# ProtectionCPLD.net
KiCad netlist of a schematic drawn in Altium Designer
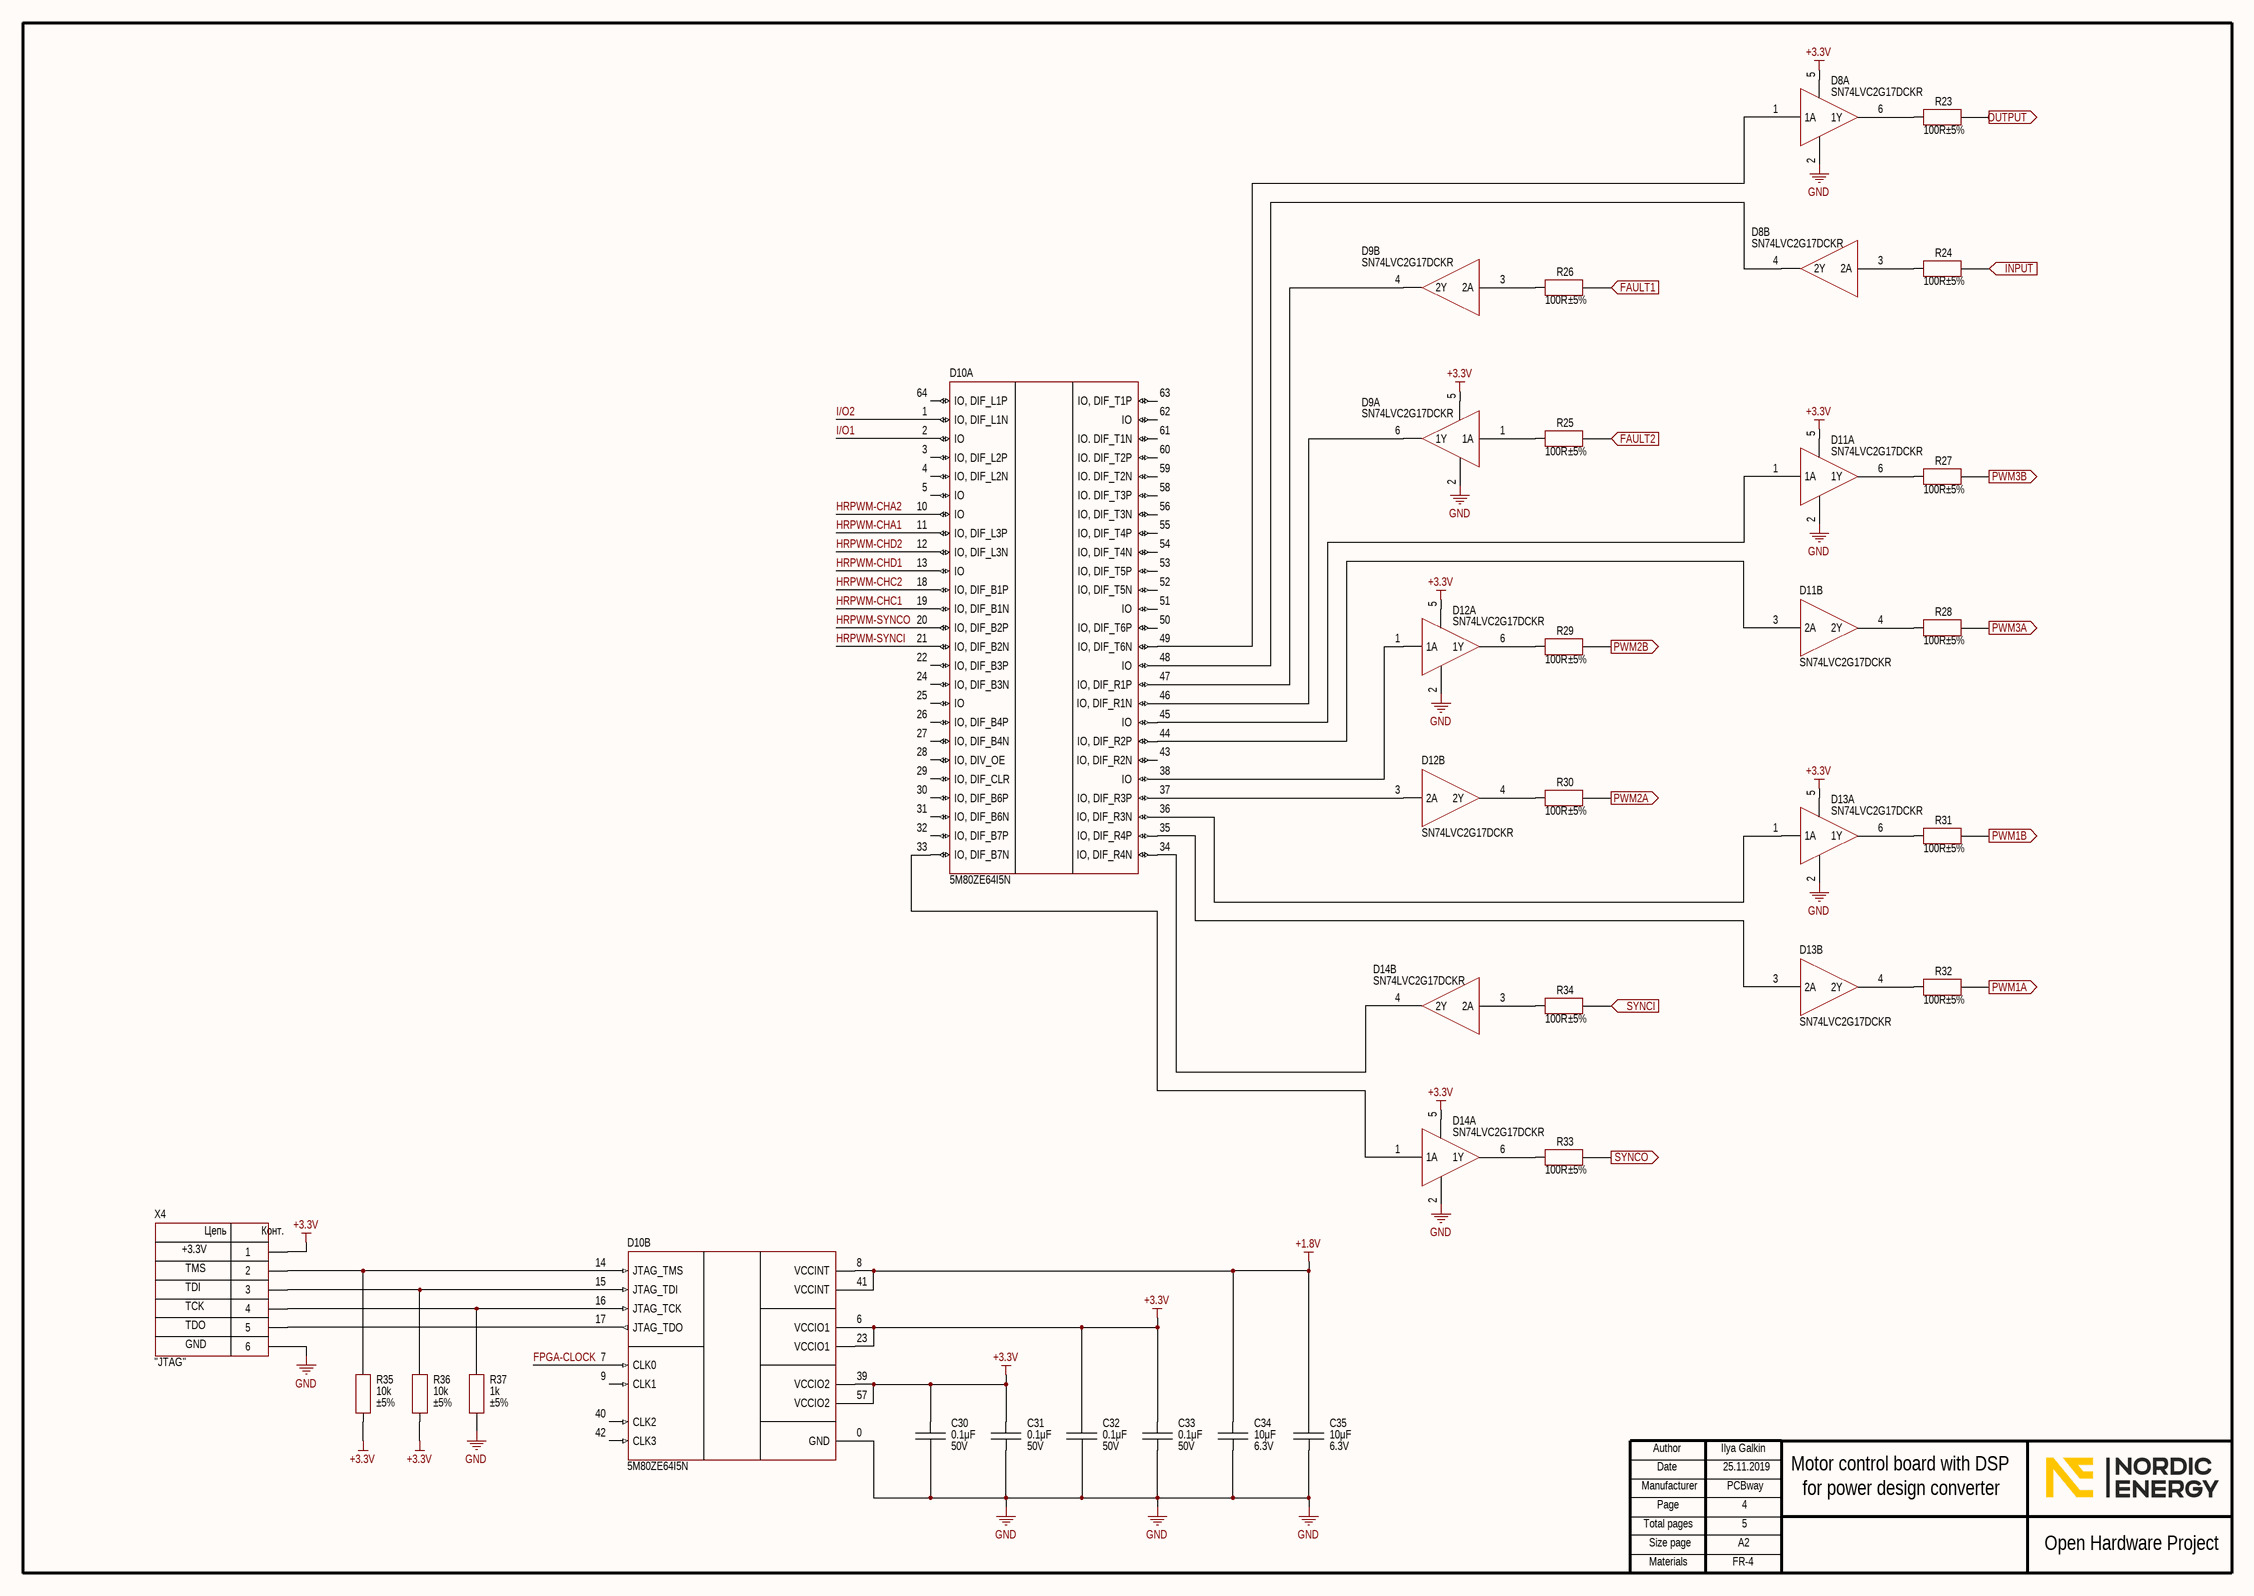
[diagram p0: ProtectionCPLD.SchDoc]

(export (version "E")
  (design (tool "Eeschema 10.0.6"))
  (components
    (comp (ref "C30")
      (value "0.1μF")
      (footprint "CAP: 0603")
      (fields
        (field (name "MANUFACTURER") "Samsung")
        (field (name "PARTNUMBER") "CL10B104KB8NNNC")
        (field (name "VALUEMANUFACTURERPARTNUMBER") "Ceramic capacitor, 0.1μF, X7R, ±10%, 50V, 0603, -55...+125°C")
        (field (name "VOLTAGE") "50V")
      )
      (libsource (lib "Capacitor") (part "Ceramic_0603"))
    )
    (comp (ref "C31")
      (value "0.1μF")
      (footprint "CAP: 0603")
      (fields
        (field (name "MANUFACTURER") "Samsung")
        (field (name "PARTNUMBER") "CL10B104KB8NNNC")
        (field (name "VALUEMANUFACTURERPARTNUMBER") "Ceramic capacitor, 0.1μF, X7R, ±10%, 50V, 0603, -55...+125°C")
        (field (name "VOLTAGE") "50V")
      )
      (libsource (lib "Capacitor") (part "Ceramic_0603"))
    )
    (comp (ref "C32")
      (value "0.1μF")
      (footprint "CAP: 0603")
      (fields
        (field (name "MANUFACTURER") "Samsung")
        (field (name "PARTNUMBER") "CL10B104KB8NNNC")
        (field (name "VALUEMANUFACTURERPARTNUMBER") "Ceramic capacitor, 0.1μF, X7R, ±10%, 50V, 0603, -55...+125°C")
        (field (name "VOLTAGE") "50V")
      )
      (libsource (lib "Capacitor") (part "Ceramic_0603"))
    )
    (comp (ref "C33")
      (value "0.1μF")
      (footprint "CAP: 0603")
      (fields
        (field (name "MANUFACTURER") "Samsung")
        (field (name "PARTNUMBER") "CL10B104KB8NNNC")
        (field (name "VALUEMANUFACTURERPARTNUMBER") "Ceramic capacitor, 0.1μF, X7R, ±10%, 50V, 0603, -55...+125°C")
        (field (name "VOLTAGE") "50V")
      )
      (libsource (lib "Capacitor") (part "Ceramic_0603"))
    )
    (comp (ref "C34")
      (value "10μF")
      (footprint "CAP: 0603")
      (fields
        (field (name "MANUFACTURER") "Samsung")
        (field (name "PARTNUMBER") "CL10B106MQ8NRNC")
        (field (name "VALUEMANUFACTURERPARTNUMBER") "Ceramic capacitor, 10μF, X7R, ±10%, 6.3V, 0603, -55...+125°C")
        (field (name "VOLTAGE") "6.3V")
      )
      (libsource (lib "Capacitor") (part "Ceramic_0603"))
    )
    (comp (ref "C35")
      (value "10μF")
      (footprint "CAP: 0603")
      (fields
        (field (name "MANUFACTURER") "Samsung")
        (field (name "PARTNUMBER") "CL10B106MQ8NRNC")
        (field (name "VALUEMANUFACTURERPARTNUMBER") "Ceramic capacitor, 10μF, X7R, ±10%, 6.3V, 0603, -55...+125°C")
        (field (name "VOLTAGE") "6.3V")
      )
      (libsource (lib "Capacitor") (part "Ceramic_0603"))
    )
    (comp (ref "D8")
      (value "~")
      (footprint "SC70-6")
      (description "Buffer")
      (fields
        (field (name "MANUFACTURER") "Texas Instruments")
        (field (name "VALUEMANUFACTURERPARTNUMBER") "IC logic buffer, 1.65...5.5V, -40...+125°C, SC-70-6")
        (field (name "PARTNUMBER") "SN74LVC2G17DCKR")
      )
      (libsource (lib "IC. Logic") (part "SN74LVC2G17DCKR"))
    )
    (comp (ref "D9")
      (value "~")
      (footprint "SC70-6")
      (description "Buffer")
      (fields
        (field (name "MANUFACTURER") "Texas Instruments")
        (field (name "VALUEMANUFACTURERPARTNUMBER") "IC logic buffer, 1.65...5.5V, -40...+125°C, SC-70-6")
        (field (name "PARTNUMBER") "SN74LVC2G17DCKR")
      )
      (libsource (lib "IC. Logic") (part "SN74LVC2G17DCKR"))
    )
    (comp (ref "D10")
      (value "~")
      (footprint "64-EQFP")
      (description "CPLD Max V")
      (fields
        (field (name "MANUFACTURER") "Intel")
        (field (name "VALUEMANUFACTURERPARTNUMBER") "IC CPLD logic, MAX V, 100MHz, 80LE, 1.71...1.89V, -40...+100°C, 64-EQFP")
        (field (name "PARTNUMBER") "5M80ZE64I5N")
      )
      (libsource (lib "") (part "5M80ZE64I5N_1"))
    )
    (comp (ref "D11")
      (value "~")
      (footprint "SC70-6")
      (description "Buffer")
      (fields
        (field (name "MANUFACTURER") "Texas Instruments")
        (field (name "VALUEMANUFACTURERPARTNUMBER") "IC logic buffer, 1.65...5.5V, -40...+125°C, SC-70-6")
        (field (name "PARTNUMBER") "SN74LVC2G17DCKR")
      )
      (libsource (lib "IC. Logic") (part "SN74LVC2G17DCKR"))
    )
    (comp (ref "D12")
      (value "~")
      (footprint "SC70-6")
      (description "Buffer")
      (fields
        (field (name "MANUFACTURER") "Texas Instruments")
        (field (name "VALUEMANUFACTURERPARTNUMBER") "IC logic buffer, 1.65...5.5V, -40...+125°C, SC-70-6")
        (field (name "PARTNUMBER") "SN74LVC2G17DCKR")
      )
      (libsource (lib "IC. Logic") (part "SN74LVC2G17DCKR"))
    )
    (comp (ref "D13")
      (value "~")
      (footprint "SC70-6")
      (description "Buffer")
      (fields
        (field (name "MANUFACTURER") "Texas Instruments")
        (field (name "VALUEMANUFACTURERPARTNUMBER") "IC logic buffer, 1.65...5.5V, -40...+125°C, SC-70-6")
        (field (name "PARTNUMBER") "SN74LVC2G17DCKR")
      )
      (libsource (lib "IC. Logic") (part "SN74LVC2G17DCKR"))
    )
    (comp (ref "D14")
      (value "~")
      (footprint "SC70-6")
      (description "Buffer")
      (fields
        (field (name "MANUFACTURER") "Texas Instruments")
        (field (name "VALUEMANUFACTURERPARTNUMBER") "IC logic buffer, 1.65...5.5V, -40...+125°C, SC-70-6")
        (field (name "PARTNUMBER") "SN74LVC2G17DCKR")
      )
      (libsource (lib "IC. Logic") (part "SN74LVC2G17DCKR"))
    )
    (comp (ref "R23")
      (value "100R")
      (footprint "RES: 0603")
      (fields
        (field (name "MANUFACTURER") "Yageo")
        (field (name "PARTNUMBER") "RC0603JR-07100RL")
        (field (name "VALUEMANUFACTURERPARTNUMBER") "Resistor film, 100R, ±5%, 0603, 0.1W, -55...+125°C")
        (field (name "TOLERANCE") "±5%")
      )
      (libsource (lib "Resistor") (part "Resistor_0603"))
    )
    (comp (ref "R24")
      (value "100R")
      (footprint "RES: 0603")
      (fields
        (field (name "MANUFACTURER") "Yageo")
        (field (name "PARTNUMBER") "RC0603JR-07100RL")
        (field (name "VALUEMANUFACTURERPARTNUMBER") "Resistor film, 100R, ±5%, 0603, 0.1W, -55...+125°C")
        (field (name "TOLERANCE") "±5%")
      )
      (libsource (lib "Resistor") (part "Resistor_0603"))
    )
    (comp (ref "R25")
      (value "100R")
      (footprint "RES: 0603")
      (fields
        (field (name "MANUFACTURER") "Yageo")
        (field (name "PARTNUMBER") "RC0603JR-07100RL")
        (field (name "VALUEMANUFACTURERPARTNUMBER") "Resistor film, 100R, ±5%, 0603, 0.1W, -55...+125°C")
        (field (name "TOLERANCE") "±5%")
      )
      (libsource (lib "Resistor") (part "Resistor_0603"))
    )
    (comp (ref "R26")
      (value "100R")
      (footprint "RES: 0603")
      (fields
        (field (name "MANUFACTURER") "Yageo")
        (field (name "PARTNUMBER") "RC0603JR-07100RL")
        (field (name "VALUEMANUFACTURERPARTNUMBER") "Resistor film, 100R, ±5%, 0603, 0.1W, -55...+125°C")
        (field (name "TOLERANCE") "±5%")
      )
      (libsource (lib "Resistor") (part "Resistor_0603"))
    )
    (comp (ref "R27")
      (value "100R")
      (footprint "RES: 0603")
      (fields
        (field (name "MANUFACTURER") "Yageo")
        (field (name "PARTNUMBER") "RC0603JR-07100RL")
        (field (name "VALUEMANUFACTURERPARTNUMBER") "Resistor film, 100R, ±5%, 0603, 0.1W, -55...+125°C")
        (field (name "TOLERANCE") "±5%")
      )
      (libsource (lib "Resistor") (part "Resistor_0603"))
    )
    (comp (ref "R28")
      (value "100R")
      (footprint "RES: 0603")
      (fields
        (field (name "MANUFACTURER") "Yageo")
        (field (name "PARTNUMBER") "RC0603JR-07100RL")
        (field (name "VALUEMANUFACTURERPARTNUMBER") "Resistor film, 100R, ±5%, 0603, 0.1W, -55...+125°C")
        (field (name "TOLERANCE") "±5%")
      )
      (libsource (lib "Resistor") (part "Resistor_0603"))
    )
    (comp (ref "R29")
      (value "100R")
      (footprint "RES: 0603")
      (fields
        (field (name "MANUFACTURER") "Yageo")
        (field (name "PARTNUMBER") "RC0603JR-07100RL")
        (field (name "VALUEMANUFACTURERPARTNUMBER") "Resistor film, 100R, ±5%, 0603, 0.1W, -55...+125°C")
        (field (name "TOLERANCE") "±5%")
      )
      (libsource (lib "Resistor") (part "Resistor_0603"))
    )
    (comp (ref "R30")
      (value "100R")
      (footprint "RES: 0603")
      (fields
        (field (name "MANUFACTURER") "Yageo")
        (field (name "PARTNUMBER") "RC0603JR-07100RL")
        (field (name "VALUEMANUFACTURERPARTNUMBER") "Resistor film, 100R, ±5%, 0603, 0.1W, -55...+125°C")
        (field (name "TOLERANCE") "±5%")
      )
      (libsource (lib "Resistor") (part "Resistor_0603"))
    )
    (comp (ref "R31")
      (value "100R")
      (footprint "RES: 0603")
      (fields
        (field (name "MANUFACTURER") "Yageo")
        (field (name "PARTNUMBER") "RC0603JR-07100RL")
        (field (name "VALUEMANUFACTURERPARTNUMBER") "Resistor film, 100R, ±5%, 0603, 0.1W, -55...+125°C")
        (field (name "TOLERANCE") "±5%")
      )
      (libsource (lib "Resistor") (part "Resistor_0603"))
    )
    (comp (ref "R32")
      (value "100R")
      (footprint "RES: 0603")
      (fields
        (field (name "MANUFACTURER") "Yageo")
        (field (name "PARTNUMBER") "RC0603JR-07100RL")
        (field (name "VALUEMANUFACTURERPARTNUMBER") "Resistor film, 100R, ±5%, 0603, 0.1W, -55...+125°C")
        (field (name "TOLERANCE") "±5%")
      )
      (libsource (lib "Resistor") (part "Resistor_0603"))
    )
    (comp (ref "R33")
      (value "100R")
      (footprint "RES: 0603")
      (fields
        (field (name "MANUFACTURER") "Yageo")
        (field (name "PARTNUMBER") "RC0603JR-07100RL")
        (field (name "VALUEMANUFACTURERPARTNUMBER") "Resistor film, 100R, ±5%, 0603, 0.1W, -55...+125°C")
        (field (name "TOLERANCE") "±5%")
      )
      (libsource (lib "Resistor") (part "Resistor_0603"))
    )
    (comp (ref "R34")
      (value "100R")
      (footprint "RES: 0603")
      (fields
        (field (name "MANUFACTURER") "Yageo")
        (field (name "PARTNUMBER") "RC0603JR-07100RL")
        (field (name "VALUEMANUFACTURERPARTNUMBER") "Resistor film, 100R, ±5%, 0603, 0.1W, -55...+125°C")
        (field (name "TOLERANCE") "±5%")
      )
      (libsource (lib "Resistor") (part "Resistor_0603"))
    )
    (comp (ref "R35")
      (value "10k")
      (footprint "RES: 0603")
      (fields
        (field (name "MANUFACTURER") "Yageo")
        (field (name "PARTNUMBER") "RC0603JR-0710KL")
        (field (name "VALUEMANUFACTURERPARTNUMBER") "Resistor film, 10k, ±5%, 0603, 0.1W, -55...+125°C")
        (field (name "TOLERANCE") "±5%")
      )
      (libsource (lib "") (part "Resistor_0603_1"))
    )
    (comp (ref "R36")
      (value "10k")
      (footprint "RES: 0603")
      (fields
        (field (name "MANUFACTURER") "Yageo")
        (field (name "PARTNUMBER") "RC0603JR-0710KL")
        (field (name "VALUEMANUFACTURERPARTNUMBER") "Resistor film, 10k, ±5%, 0603, 0.1W, -55...+125°C")
        (field (name "TOLERANCE") "±5%")
      )
      (libsource (lib "") (part "Resistor_0603_1"))
    )
    (comp (ref "R37")
      (value "1k")
      (footprint "RES: 0603")
      (fields
        (field (name "MANUFACTURER") "Yageo")
        (field (name "PARTNUMBER") "RC0603JR-071KL")
        (field (name "VALUEMANUFACTURERPARTNUMBER") "Resistor film, 1k, ±5%, 0603, 0.1W, -55...+125°C")
        (field (name "TOLERANCE") "±5%")
      )
      (libsource (lib "") (part "Resistor_0603_1"))
    )
    (comp (ref "X4")
      (value "~")
      (footprint "CON: SM06B-GHS")
      (fields
        (field (name "MANUFACTURER") "JST")
        (field (name "VALUEMANUFACTURERPARTNUMBER") "Connector, 6pin, 1.25mm, 50VDC, 1A")
        (field (name "PARTNUMBER") "SM06B-GHS")
        (field (name "COMMENTTEXT") "\"JTAG\"")
      )
      (libsource (lib "Connector") (part "Connector_SM06B"))
    )
  )
  (nets
    (net (code "1") (name "+1.8V") (class "Default")
      (node (ref "C34") (pin "2") (pinfunction "2_2") (pintype "power_in"))
      (node (ref "C35") (pin "2") (pinfunction "2_2") (pintype "power_in"))
      (node (ref "D10") (pin "41") (pinfunction "VCCINT_41") (pintype "power_in"))
      (node (ref "D10") (pin "8") (pinfunction "VCCINT_8") (pintype "power_in"))
    )
    (net (code "2") (name "+3.3V") (class "Default")
      (node (ref "C30") (pin "2") (pinfunction "2_2") (pintype "power_in"))
      (node (ref "C31") (pin "2") (pinfunction "2_2") (pintype "power_in"))
      (node (ref "C32") (pin "2") (pinfunction "2_2") (pintype "power_in"))
      (node (ref "C33") (pin "2") (pinfunction "2_2") (pintype "power_in"))
      (node (ref "D10") (pin "23") (pinfunction "VCCIO1_23") (pintype "power_in"))
      (node (ref "D10") (pin "39") (pinfunction "VCCIO2_39") (pintype "power_in"))
      (node (ref "D10") (pin "57") (pinfunction "VCCIO2_57") (pintype "power_in"))
      (node (ref "D10") (pin "6") (pinfunction "VCCIO1_6") (pintype "power_in"))
      (node (ref "D11") (pin "5") (pintype "passive"))
      (node (ref "D12") (pin "5") (pintype "passive"))
      (node (ref "D13") (pin "5") (pintype "passive"))
      (node (ref "D14") (pin "5") (pintype "passive"))
      (node (ref "D8") (pin "5") (pintype "passive"))
      (node (ref "D9") (pin "5") (pintype "passive"))
      (node (ref "R35") (pin "1") (pinfunction "1_1") (pintype "passive"))
      (node (ref "R36") (pin "1") (pinfunction "1_1") (pintype "passive"))
      (node (ref "X4") (pin "1") (pinfunction "1_1") (pintype "passive"))
    )
    (net (code "3") (name "/FAULT1") (class "Default")
      (node (ref "R26") (pin "2") (pinfunction "2_2") (pintype "passive"))
    )
    (net (code "4") (name "/FAULT2") (class "Default")
      (node (ref "R25") (pin "2") (pinfunction "2_2") (pintype "passive"))
    )
    (net (code "5") (name "/FPGA-CLOCK") (class "Default")
      (node (ref "D10") (pin "7") (pinfunction "CLK0_7") (pintype "input"))
    )
    (net (code "6") (name "/HRPWM-CHA1") (class "Default")
      (node (ref "D10") (pin "11") (pinfunction "IO,_DIF_L3P_11") (pintype "bidirectional"))
    )
    (net (code "7") (name "/HRPWM-CHA2") (class "Default")
      (node (ref "D10") (pin "10") (pinfunction "IO_10") (pintype "bidirectional"))
    )
    (net (code "8") (name "/HRPWM-CHC1") (class "Default")
      (node (ref "D10") (pin "19") (pinfunction "IO,_DIF_B1N_19") (pintype "bidirectional"))
    )
    (net (code "9") (name "/HRPWM-CHC2") (class "Default")
      (node (ref "D10") (pin "18") (pinfunction "IO,_DIF_B1P_18") (pintype "bidirectional"))
    )
    (net (code "10") (name "/HRPWM-CHD1") (class "Default")
      (node (ref "D10") (pin "13") (pinfunction "IO_13") (pintype "bidirectional"))
    )
    (net (code "11") (name "/HRPWM-CHD2") (class "Default")
      (node (ref "D10") (pin "12") (pinfunction "IO,_DIF_L3N_12") (pintype "bidirectional"))
    )
    (net (code "12") (name "/HRPWM-SYNCI") (class "Default")
      (node (ref "D10") (pin "21") (pinfunction "IO,_DIF_B2N_21") (pintype "bidirectional"))
    )
    (net (code "13") (name "/HRPWM-SYNCO") (class "Default")
      (node (ref "D10") (pin "20") (pinfunction "IO,_DIF_B2P_20") (pintype "bidirectional"))
    )
    (net (code "14") (name "/INPUT") (class "Default")
      (node (ref "R24") (pin "2") (pinfunction "2_2") (pintype "passive"))
    )
    (net (code "15") (name "/I{slash}O1") (class "Default")
      (node (ref "D10") (pin "2") (pinfunction "IO_2") (pintype "bidirectional"))
    )
    (net (code "16") (name "/I{slash}O2") (class "Default")
      (node (ref "D10") (pin "1") (pinfunction "IO,_DIF_L1N_1") (pintype "bidirectional"))
    )
    (net (code "17") (name "/OUTPUT") (class "Default")
      (node (ref "R23") (pin "2") (pinfunction "2_2") (pintype "passive"))
    )
    (net (code "18") (name "/PWM1A") (class "Default")
      (node (ref "R32") (pin "2") (pinfunction "2_2") (pintype "passive"))
    )
    (net (code "19") (name "/PWM1B") (class "Default")
      (node (ref "R31") (pin "2") (pinfunction "2_2") (pintype "passive"))
    )
    (net (code "20") (name "/PWM2A") (class "Default")
      (node (ref "R30") (pin "2") (pinfunction "2_2") (pintype "passive"))
    )
    (net (code "21") (name "/PWM2B") (class "Default")
      (node (ref "R29") (pin "2") (pinfunction "2_2") (pintype "passive"))
    )
    (net (code "22") (name "/PWM3A") (class "Default")
      (node (ref "R28") (pin "2") (pinfunction "2_2") (pintype "passive"))
    )
    (net (code "23") (name "/PWM3B") (class "Default")
      (node (ref "R27") (pin "2") (pinfunction "2_2") (pintype "passive"))
    )
    (net (code "24") (name "/SYNCI") (class "Default")
      (node (ref "R34") (pin "2") (pinfunction "2_2") (pintype "passive"))
    )
    (net (code "25") (name "/SYNCO") (class "Default")
      (node (ref "R33") (pin "2") (pinfunction "2_2") (pintype "passive"))
    )
    (net (code "26") (name "GND") (class "Default")
      (node (ref "C30") (pin "1") (pinfunction "1_1") (pintype "power_in"))
      (node (ref "C31") (pin "1") (pinfunction "1_1") (pintype "power_in"))
      (node (ref "C32") (pin "1") (pinfunction "1_1") (pintype "power_in"))
      (node (ref "C33") (pin "1") (pinfunction "1_1") (pintype "power_in"))
      (node (ref "C34") (pin "1") (pinfunction "1_1") (pintype "power_in"))
      (node (ref "C35") (pin "1") (pinfunction "1_1") (pintype "power_in"))
      (node (ref "D10") (pin "0") (pinfunction "GND_0") (pintype "power_in"))
      (node (ref "D11") (pin "2") (pintype "passive"))
      (node (ref "D12") (pin "2") (pintype "passive"))
      (node (ref "D13") (pin "2") (pintype "passive"))
      (node (ref "D14") (pin "2") (pintype "passive"))
      (node (ref "D8") (pin "2") (pintype "passive"))
      (node (ref "D9") (pin "2") (pintype "passive"))
      (node (ref "R37") (pin "1") (pinfunction "1_1") (pintype "passive"))
      (node (ref "X4") (pin "6") (pinfunction "6_6") (pintype "power_in"))
    )
    (net (code "27") (name "Net-(D8A-1Y)") (class "Default")
      (node (ref "D8") (pin "6") (pinfunction "1Y_6") (pintype "passive"))
      (node (ref "R23") (pin "1") (pinfunction "1_1") (pintype "passive"))
    )
    (net (code "28") (name "Net-(D8B-2A)") (class "Default")
      (node (ref "D8") (pin "3") (pinfunction "2A_3") (pintype "passive"))
      (node (ref "R24") (pin "1") (pinfunction "1_1") (pintype "passive"))
    )
    (net (code "29") (name "Net-(D8B-2Y)") (class "Default")
      (node (ref "D10") (pin "48") (pinfunction "IO_48") (pintype "bidirectional"))
      (node (ref "D8") (pin "4") (pinfunction "2Y_4") (pintype "passive"))
    )
    (net (code "30") (name "Net-(D9A-1A)") (class "Default")
      (node (ref "D9") (pin "1") (pinfunction "1A_1") (pintype "passive"))
      (node (ref "R25") (pin "1") (pinfunction "1_1") (pintype "passive"))
    )
    (net (code "31") (name "Net-(D9B-2A)") (class "Default")
      (node (ref "D9") (pin "3") (pinfunction "2A_3") (pintype "passive"))
      (node (ref "R26") (pin "1") (pinfunction "1_1") (pintype "passive"))
    )
    (net (code "32") (name "Net-(D10A-IO,_DIF_B7N)") (class "Default")
      (node (ref "D10") (pin "33") (pinfunction "IO,_DIF_B7N_33") (pintype "bidirectional"))
      (node (ref "D14") (pin "1") (pinfunction "1A_1") (pintype "passive"))
    )
    (net (code "33") (name "Net-(D10A-IO,_DIF_R1N)") (class "Default")
      (node (ref "D10") (pin "46") (pinfunction "IO,_DIF_R1N_46") (pintype "bidirectional"))
      (node (ref "D9") (pin "6") (pinfunction "1Y_6") (pintype "passive"))
    )
    (net (code "34") (name "Net-(D10A-IO,_DIF_R1P)") (class "Default")
      (node (ref "D10") (pin "47") (pinfunction "IO,_DIF_R1P_47") (pintype "bidirectional"))
      (node (ref "D9") (pin "4") (pinfunction "2Y_4") (pintype "passive"))
    )
    (net (code "35") (name "Net-(D10A-IO,_DIF_R2P)") (class "Default")
      (node (ref "D10") (pin "44") (pinfunction "IO,_DIF_R2P_44") (pintype "bidirectional"))
      (node (ref "D11") (pin "3") (pinfunction "2A_3") (pintype "passive"))
    )
    (net (code "36") (name "Net-(D10A-IO,_DIF_R3N)") (class "Default")
      (node (ref "D10") (pin "36") (pinfunction "IO,_DIF_R3N_36") (pintype "bidirectional"))
      (node (ref "D13") (pin "1") (pinfunction "1A_1") (pintype "passive"))
    )
    (net (code "37") (name "Net-(D10A-IO,_DIF_R3P)") (class "Default")
      (node (ref "D10") (pin "37") (pinfunction "IO,_DIF_R3P_37") (pintype "bidirectional"))
      (node (ref "D12") (pin "3") (pinfunction "2A_3") (pintype "passive"))
    )
    (net (code "38") (name "Net-(D10A-IO,_DIF_R4N)") (class "Default")
      (node (ref "D10") (pin "34") (pinfunction "IO,_DIF_R4N_34") (pintype "bidirectional"))
      (node (ref "D14") (pin "4") (pinfunction "2Y_4") (pintype "passive"))
    )
    (net (code "39") (name "Net-(D10A-IO,_DIF_R4P)") (class "Default")
      (node (ref "D10") (pin "35") (pinfunction "IO,_DIF_R4P_35") (pintype "bidirectional"))
      (node (ref "D13") (pin "3") (pinfunction "2A_3") (pintype "passive"))
    )
    (net (code "40") (name "Net-(D10A-IO,_DIF_T6N)") (class "Default")
      (node (ref "D10") (pin "49") (pinfunction "IO,_DIF_T6N_49") (pintype "bidirectional"))
      (node (ref "D8") (pin "1") (pinfunction "1A_1") (pintype "passive"))
    )
    (net (code "41") (name "Net-(D10B-JTAG_TCK)") (class "Default")
      (node (ref "D10") (pin "16") (pinfunction "JTAG_TCK_16") (pintype "input"))
      (node (ref "R37") (pin "2") (pinfunction "2_2") (pintype "passive"))
      (node (ref "X4") (pin "4") (pinfunction "4_4") (pintype "power_in"))
    )
    (net (code "42") (name "Net-(D10B-JTAG_TDI)") (class "Default")
      (node (ref "D10") (pin "15") (pinfunction "JTAG_TDI_15") (pintype "input"))
      (node (ref "R36") (pin "2") (pinfunction "2_2") (pintype "passive"))
      (node (ref "X4") (pin "3") (pinfunction "3_3") (pintype "power_in"))
    )
    (net (code "43") (name "Net-(D10B-JTAG_TDO)") (class "Default")
      (node (ref "D10") (pin "17") (pinfunction "JTAG_TDO_17") (pintype "output"))
      (node (ref "X4") (pin "5") (pinfunction "5_5") (pintype "power_in"))
    )
    (net (code "44") (name "Net-(D10B-JTAG_TMS)") (class "Default")
      (node (ref "D10") (pin "14") (pinfunction "JTAG_TMS_14") (pintype "input"))
      (node (ref "R35") (pin "2") (pinfunction "2_2") (pintype "passive"))
      (node (ref "X4") (pin "2") (pinfunction "2_2") (pintype "passive"))
    )
    (net (code "45") (name "Net-(D11A-1A)") (class "Default")
      (node (ref "D10") (pin "45") (pinfunction "IO_45") (pintype "bidirectional"))
      (node (ref "D11") (pin "1") (pinfunction "1A_1") (pintype "passive"))
    )
    (net (code "46") (name "Net-(D11A-1Y)") (class "Default")
      (node (ref "D11") (pin "6") (pinfunction "1Y_6") (pintype "passive"))
      (node (ref "R27") (pin "1") (pinfunction "1_1") (pintype "passive"))
    )
    (net (code "47") (name "Net-(D11B-2Y)") (class "Default")
      (node (ref "D11") (pin "4") (pinfunction "2Y_4") (pintype "passive"))
      (node (ref "R28") (pin "1") (pinfunction "1_1") (pintype "passive"))
    )
    (net (code "48") (name "Net-(D12A-1A)") (class "Default")
      (node (ref "D10") (pin "38") (pinfunction "IO_38") (pintype "bidirectional"))
      (node (ref "D12") (pin "1") (pinfunction "1A_1") (pintype "passive"))
    )
    (net (code "49") (name "Net-(D12A-1Y)") (class "Default")
      (node (ref "D12") (pin "6") (pinfunction "1Y_6") (pintype "passive"))
      (node (ref "R29") (pin "1") (pinfunction "1_1") (pintype "passive"))
    )
    (net (code "50") (name "Net-(D12B-2Y)") (class "Default")
      (node (ref "D12") (pin "4") (pinfunction "2Y_4") (pintype "passive"))
      (node (ref "R30") (pin "1") (pinfunction "1_1") (pintype "passive"))
    )
    (net (code "51") (name "Net-(D13A-1Y)") (class "Default")
      (node (ref "D13") (pin "6") (pinfunction "1Y_6") (pintype "passive"))
      (node (ref "R31") (pin "1") (pinfunction "1_1") (pintype "passive"))
    )
    (net (code "52") (name "Net-(D13B-2Y)") (class "Default")
      (node (ref "D13") (pin "4") (pinfunction "2Y_4") (pintype "passive"))
      (node (ref "R32") (pin "1") (pinfunction "1_1") (pintype "passive"))
    )
    (net (code "53") (name "Net-(D14A-1Y)") (class "Default")
      (node (ref "D14") (pin "6") (pinfunction "1Y_6") (pintype "passive"))
      (node (ref "R33") (pin "1") (pinfunction "1_1") (pintype "passive"))
    )
    (net (code "54") (name "Net-(D14B-2A)") (class "Default")
      (node (ref "D14") (pin "3") (pinfunction "2A_3") (pintype "passive"))
      (node (ref "R34") (pin "1") (pinfunction "1_1") (pintype "passive"))
    )
    (net (code "55") (name "unconnected-(D10A-IO,_DIF_B3N-Pad24)") (class "Default")
      (node (ref "D10") (pin "24") (pinfunction "IO,_DIF_B3N_24") (pintype "bidirectional"))
    )
    (net (code "56") (name "unconnected-(D10A-IO,_DIF_B3P-Pad22)") (class "Default")
      (node (ref "D10") (pin "22") (pinfunction "IO,_DIF_B3P_22") (pintype "bidirectional"))
    )
    (net (code "57") (name "unconnected-(D10A-IO,_DIF_B4N-Pad27)") (class "Default")
      (node (ref "D10") (pin "27") (pinfunction "IO,_DIF_B4N_27") (pintype "bidirectional"))
    )
    (net (code "58") (name "unconnected-(D10A-IO,_DIF_B4P-Pad26)") (class "Default")
      (node (ref "D10") (pin "26") (pinfunction "IO,_DIF_B4P_26") (pintype "bidirectional"))
    )
    (net (code "59") (name "unconnected-(D10A-IO,_DIF_B6N-Pad31)") (class "Default")
      (node (ref "D10") (pin "31") (pinfunction "IO,_DIF_B6N_31") (pintype "bidirectional"))
    )
    (net (code "60") (name "unconnected-(D10A-IO,_DIF_B6P-Pad30)") (class "Default")
      (node (ref "D10") (pin "30") (pinfunction "IO,_DIF_B6P_30") (pintype "bidirectional"))
    )
    (net (code "61") (name "unconnected-(D10A-IO,_DIF_B7P-Pad32)") (class "Default")
      (node (ref "D10") (pin "32") (pinfunction "IO,_DIF_B7P_32") (pintype "bidirectional"))
    )
    (net (code "62") (name "unconnected-(D10A-IO,_DIF_CLR-Pad29)") (class "Default")
      (node (ref "D10") (pin "29") (pinfunction "IO,_DIF_CLR_29") (pintype "bidirectional"))
    )
    (net (code "63") (name "unconnected-(D10A-IO,_DIF_L1P-Pad64)") (class "Default")
      (node (ref "D10") (pin "64") (pinfunction "IO,_DIF_L1P_64") (pintype "bidirectional"))
    )
    (net (code "64") (name "unconnected-(D10A-IO,_DIF_L2N-Pad4)") (class "Default")
      (node (ref "D10") (pin "4") (pinfunction "IO,_DIF_L2N_4") (pintype "bidirectional"))
    )
    (net (code "65") (name "unconnected-(D10A-IO,_DIF_L2P-Pad3)") (class "Default")
      (node (ref "D10") (pin "3") (pinfunction "IO,_DIF_L2P_3") (pintype "bidirectional"))
    )
    (net (code "66") (name "unconnected-(D10A-IO,_DIF_R2N-Pad43)") (class "Default")
      (node (ref "D10") (pin "43") (pinfunction "IO,_DIF_R2N_43") (pintype "bidirectional"))
    )
    (net (code "67") (name "unconnected-(D10A-IO,_DIF_T1P-Pad63)") (class "Default")
      (node (ref "D10") (pin "63") (pinfunction "IO,_DIF_T1P_63") (pintype "bidirectional"))
    )
    (net (code "68") (name "unconnected-(D10A-IO,_DIF_T3N-Pad56)") (class "Default")
      (node (ref "D10") (pin "56") (pinfunction "IO,_DIF_T3N_56") (pintype "bidirectional"))
    )
    (net (code "69") (name "unconnected-(D10A-IO,_DIF_T4N-Pad54)") (class "Default")
      (node (ref "D10") (pin "54") (pinfunction "IO,_DIF_T4N_54") (pintype "bidirectional"))
    )
    (net (code "70") (name "unconnected-(D10A-IO,_DIF_T4P-Pad55)") (class "Default")
      (node (ref "D10") (pin "55") (pinfunction "IO,_DIF_T4P_55") (pintype "bidirectional"))
    )
    (net (code "71") (name "unconnected-(D10A-IO,_DIF_T5N-Pad52)") (class "Default")
      (node (ref "D10") (pin "52") (pinfunction "IO,_DIF_T5N_52") (pintype "bidirectional"))
    )
    (net (code "72") (name "unconnected-(D10A-IO,_DIF_T5P-Pad53)") (class "Default")
      (node (ref "D10") (pin "53") (pinfunction "IO,_DIF_T5P_53") (pintype "bidirectional"))
    )
    (net (code "73") (name "unconnected-(D10A-IO,_DIF_T6P-Pad50)") (class "Default")
      (node (ref "D10") (pin "50") (pinfunction "IO,_DIF_T6P_50") (pintype "bidirectional"))
    )
    (net (code "74") (name "unconnected-(D10A-IO,_DIV_OE-Pad28)") (class "Default")
      (node (ref "D10") (pin "28") (pinfunction "IO,_DIV_OE_28") (pintype "bidirectional"))
    )
    (net (code "75") (name "unconnected-(D10A-IO-Pad5)") (class "Default")
      (node (ref "D10") (pin "5") (pinfunction "IO_5") (pintype "bidirectional"))
    )
    (net (code "76") (name "unconnected-(D10A-IO-Pad25)") (class "Default")
      (node (ref "D10") (pin "25") (pinfunction "IO_25") (pintype "bidirectional"))
    )
    (net (code "77") (name "unconnected-(D10A-IO-Pad51)") (class "Default")
      (node (ref "D10") (pin "51") (pinfunction "IO_51") (pintype "bidirectional"))
    )
    (net (code "78") (name "unconnected-(D10A-IO-Pad62)") (class "Default")
      (node (ref "D10") (pin "62") (pinfunction "IO_62") (pintype "bidirectional"))
    )
    (net (code "79") (name "unconnected-(D10A-IO._DIF_T1N-Pad61)") (class "Default")
      (node (ref "D10") (pin "61") (pinfunction "IO._DIF_T1N_61") (pintype "bidirectional"))
    )
    (net (code "80") (name "unconnected-(D10A-IO._DIF_T2N-Pad59)") (class "Default")
      (node (ref "D10") (pin "59") (pinfunction "IO._DIF_T2N_59") (pintype "bidirectional"))
    )
    (net (code "81") (name "unconnected-(D10A-IO._DIF_T2P-Pad60)") (class "Default")
      (node (ref "D10") (pin "60") (pinfunction "IO._DIF_T2P_60") (pintype "bidirectional"))
    )
    (net (code "82") (name "unconnected-(D10A-IO._DIF_T3P-Pad58)") (class "Default")
      (node (ref "D10") (pin "58") (pinfunction "IO._DIF_T3P_58") (pintype "bidirectional"))
    )
    (net (code "83") (name "unconnected-(D10B-CLK1-Pad9)") (class "Default")
      (node (ref "D10") (pin "9") (pinfunction "CLK1_9") (pintype "input"))
    )
    (net (code "84") (name "unconnected-(D10B-CLK2-Pad40)") (class "Default")
      (node (ref "D10") (pin "40") (pinfunction "CLK2_40") (pintype "input"))
    )
    (net (code "85") (name "unconnected-(D10B-CLK3-Pad42)") (class "Default")
      (node (ref "D10") (pin "42") (pinfunction "CLK3_42") (pintype "input"))
    )
  )
)
